# projekt.net
KiCad netlist of a schematic drawn in EAGLE
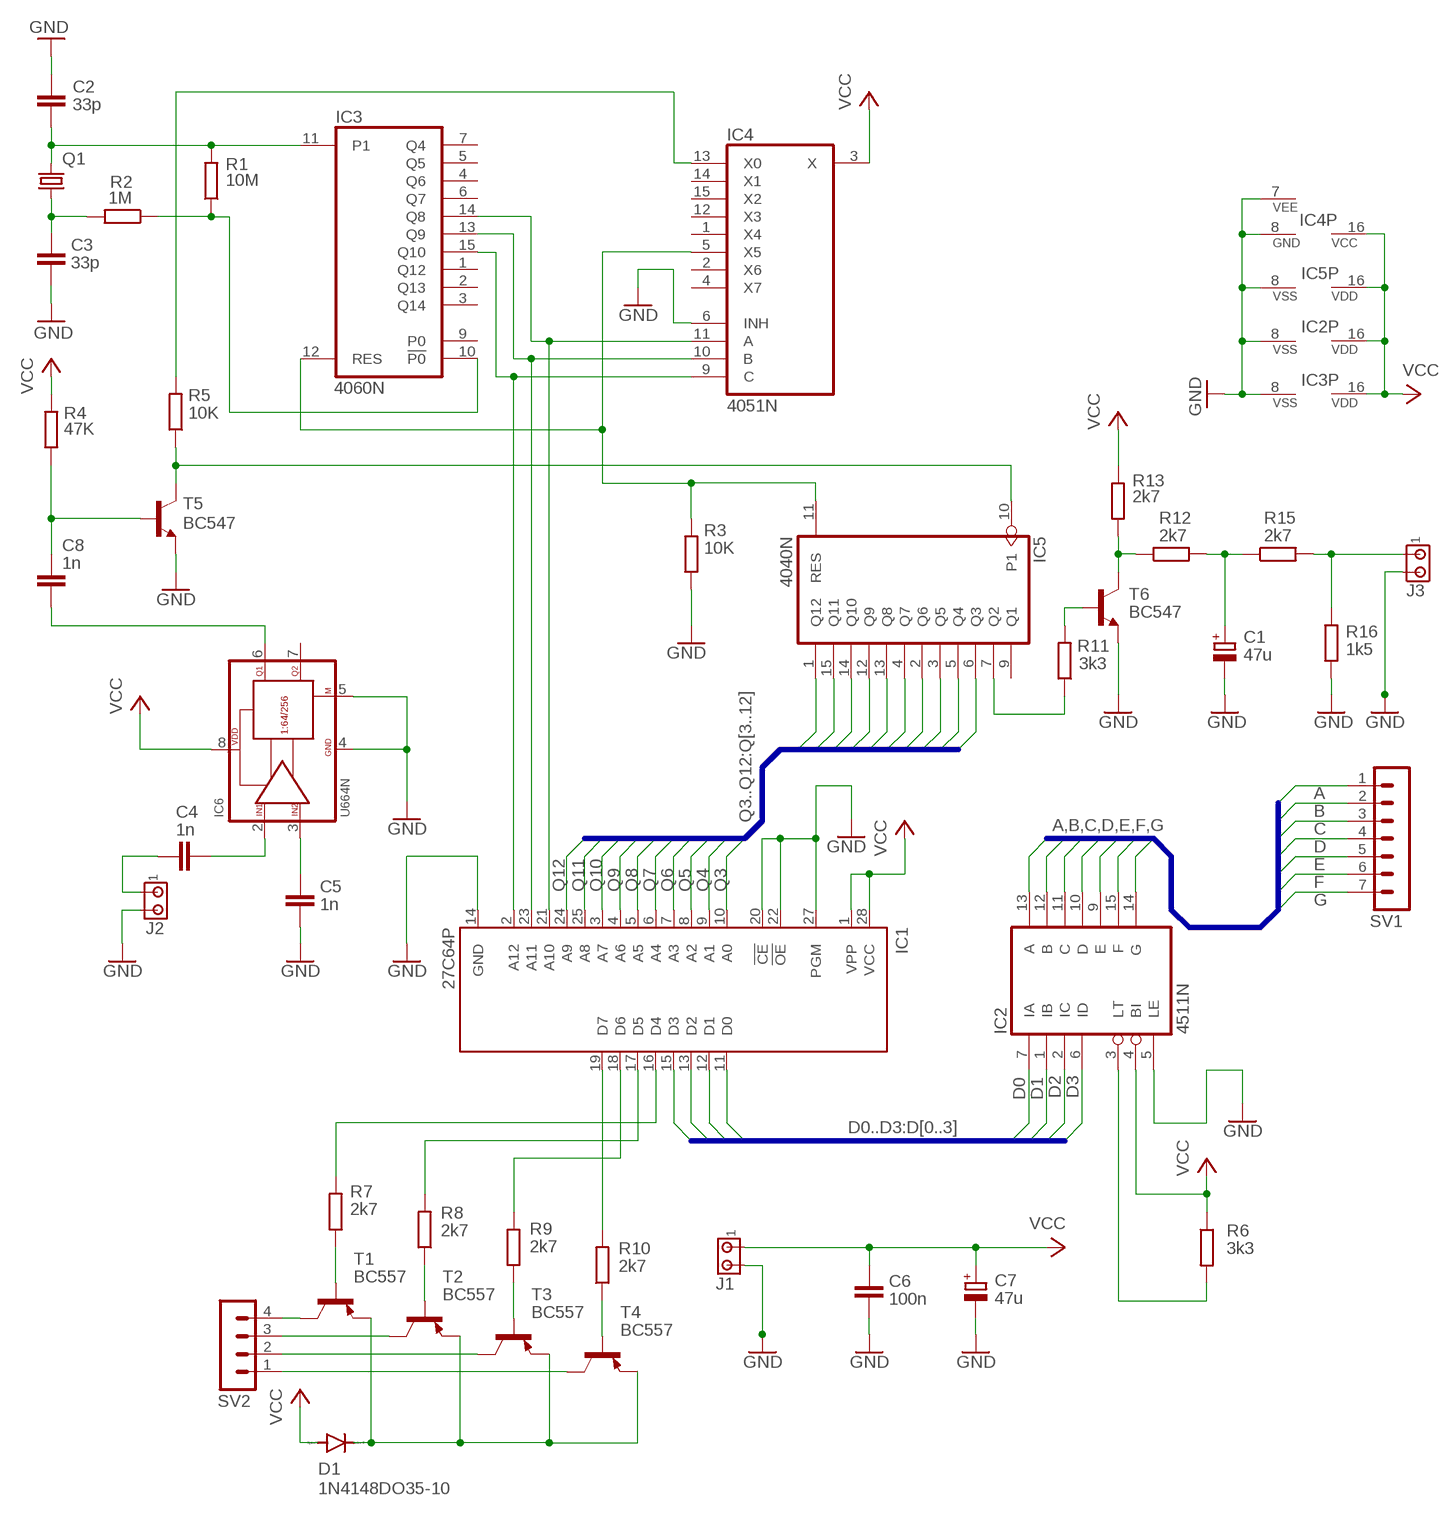
[diagram p0: schematic, sheet 1]

(export (version "E")
  (design (tool "Eeschema 10.0.6"))
  (components
    (comp (ref "C1")
      (value "47u")
      (footprint "eagle-import:E2,5-6")
      (libsource (lib "eagle-import") (part "CPOL-EUE2.5-6"))
    )
    (comp (ref "C2")
      (value "33p")
      (footprint "eagle-import:C025-025X050")
      (libsource (lib "eagle-import") (part "C-EU025-025X050"))
    )
    (comp (ref "C3")
      (value "33p")
      (footprint "eagle-import:C025-025X050")
      (libsource (lib "eagle-import") (part "C-EU025-025X050"))
    )
    (comp (ref "C4")
      (value "1n")
      (footprint "eagle-import:C025-025X050")
      (libsource (lib "eagle-import") (part "C-EU025-025X050"))
    )
    (comp (ref "C5")
      (value "1n")
      (footprint "eagle-import:C025-025X050")
      (libsource (lib "eagle-import") (part "C-EU025-025X050"))
    )
    (comp (ref "C6")
      (value "100n")
      (footprint "eagle-import:C025-025X050")
      (libsource (lib "eagle-import") (part "C-EU025-025X050"))
    )
    (comp (ref "C7")
      (value "47u")
      (footprint "eagle-import:E2,5-6")
      (libsource (lib "eagle-import") (part "CPOL-EUE2.5-6"))
    )
    (comp (ref "C8")
      (value "1n")
      (footprint "eagle-import:C025-025X050")
      (libsource (lib "eagle-import") (part "C-EU025-025X050"))
    )
    (comp (ref "D1")
      (value "1N4148DO35-10")
      (footprint "eagle-import:DO35-10")
      (libsource (lib "eagle-import") (part "1N4148DO35-10"))
    )
    (comp (ref "IC1")
      (value "27C64P")
      (footprint "eagle-import:DIL28-6")
      (fields (field (name "MF") "Arrow Electronics") (field (name "MPN") "M27C64A-10F1"))
      (libsource (lib "eagle-import") (part "2764PC"))
    )
    (comp (ref "IC2")
      (value "4511N")
      (footprint "eagle-import:DIL16")
      (libsource (lib "eagle-import") (part "4511N"))
    )
    (comp (ref "IC3")
      (value "4060N")
      (footprint "eagle-import:DIL16")
      (libsource (lib "eagle-import") (part "4060N"))
    )
    (comp (ref "IC4")
      (value "4051N")
      (footprint "eagle-import:DIL16")
      (libsource (lib "eagle-import") (part "4051N"))
    )
    (comp (ref "IC5")
      (value "4040N")
      (footprint "eagle-import:DIL16")
      (libsource (lib "eagle-import") (part "4040N"))
    )
    (comp (ref "IC6")
      (value "U664N")
      (footprint "eagle-import:DIL08")
      (libsource (lib "eagle-import") (part "U664N"))
    )
    (comp (ref "J1")
      (value "MTA02-100")
      (footprint "eagle-import:10X02MTA")
      (libsource (lib "eagle-import") (part "MTA02-100"))
    )
    (comp (ref "J2")
      (value "MTA02-100")
      (footprint "eagle-import:10X02MTA")
      (libsource (lib "eagle-import") (part "MTA02-100"))
    )
    (comp (ref "J3")
      (value "MTA02-100")
      (footprint "eagle-import:10X02MTA")
      (libsource (lib "eagle-import") (part "MTA02-100"))
    )
    (comp (ref "Q1")
      (value "CRYSTALHC49S")
      (footprint "eagle-import:HC49_S")
      (libsource (lib "eagle-import") (part "CRYSTALHC49S"))
    )
    (comp (ref "R1")
      (value "10M")
      (footprint "eagle-import:0207_10")
      (libsource (lib "eagle-import") (part "R-EU_0207/10"))
    )
    (comp (ref "R2")
      (value "1M")
      (footprint "eagle-import:0207_10")
      (libsource (lib "eagle-import") (part "R-EU_0207/10"))
    )
    (comp (ref "R3")
      (value "10K")
      (footprint "eagle-import:0207_10")
      (libsource (lib "eagle-import") (part "R-EU_0207/10"))
    )
    (comp (ref "R4")
      (value "47K")
      (footprint "eagle-import:0207_10")
      (libsource (lib "eagle-import") (part "R-EU_0207/10"))
    )
    (comp (ref "R5")
      (value "10K")
      (footprint "eagle-import:0207_10")
      (libsource (lib "eagle-import") (part "R-EU_0207/10"))
    )
    (comp (ref "R6")
      (value "3k3")
      (footprint "eagle-import:0207_10")
      (libsource (lib "eagle-import") (part "R-EU_0207/10"))
    )
    (comp (ref "R7")
      (value "2k7")
      (footprint "eagle-import:0207_10")
      (libsource (lib "eagle-import") (part "R-EU_0207/10"))
    )
    (comp (ref "R8")
      (value "2k7")
      (footprint "eagle-import:0207_10")
      (libsource (lib "eagle-import") (part "R-EU_0207/10"))
    )
    (comp (ref "R9")
      (value "2k7")
      (footprint "eagle-import:0207_10")
      (libsource (lib "eagle-import") (part "R-EU_0207/10"))
    )
    (comp (ref "R10")
      (value "2k7")
      (footprint "eagle-import:0207_10")
      (libsource (lib "eagle-import") (part "R-EU_0207/10"))
    )
    (comp (ref "R11")
      (value "3k3")
      (footprint "eagle-import:0207_10")
      (libsource (lib "eagle-import") (part "R-EU_0207/10"))
    )
    (comp (ref "R12")
      (value "2k7")
      (footprint "eagle-import:0207_10")
      (libsource (lib "eagle-import") (part "R-EU_0207/10"))
    )
    (comp (ref "R13")
      (value "2k7")
      (footprint "eagle-import:0207_10")
      (libsource (lib "eagle-import") (part "R-EU_0207/10"))
    )
    (comp (ref "R15")
      (value "2k7")
      (footprint "eagle-import:0207_10")
      (libsource (lib "eagle-import") (part "R-EU_0207/10"))
    )
    (comp (ref "R16")
      (value "1k5")
      (footprint "eagle-import:0207_10")
      (libsource (lib "eagle-import") (part "R-EU_0207/10"))
    )
    (comp (ref "SV1")
      (value "MA07-1")
      (footprint "eagle-import:MA07-1")
      (libsource (lib "eagle-import") (part "MA07-1"))
    )
    (comp (ref "SV2")
      (value "MA04-1")
      (footprint "eagle-import:MA04-1")
      (libsource (lib "eagle-import") (part "MA04-1"))
    )
    (comp (ref "T1")
      (value "BC557")
      (footprint "eagle-import:TO92")
      (libsource (lib "eagle-import") (part "BC557"))
    )
    (comp (ref "T2")
      (value "BC557")
      (footprint "eagle-import:TO92")
      (libsource (lib "eagle-import") (part "BC557"))
    )
    (comp (ref "T3")
      (value "BC557")
      (footprint "eagle-import:TO92")
      (libsource (lib "eagle-import") (part "BC557"))
    )
    (comp (ref "T4")
      (value "BC557")
      (footprint "eagle-import:TO92")
      (libsource (lib "eagle-import") (part "BC557"))
    )
    (comp (ref "T5")
      (value "BC547")
      (footprint "eagle-import:TO92")
      (libsource (lib "eagle-import") (part "BC547"))
    )
    (comp (ref "T6")
      (value "BC547")
      (footprint "eagle-import:TO92")
      (libsource (lib "eagle-import") (part "BC547"))
    )
  )
  (nets
    (net (code "15") (name "/A") (class "Default")
      (node (ref "IC2") (pin "13") (pinfunction "A_13") (pintype "output"))
      (node (ref "SV1") (pin "1") (pinfunction "1_1") (pintype "passive"))
    )
    (net (code "16") (name "/B") (class "Default")
      (node (ref "IC2") (pin "12") (pinfunction "B_12") (pintype "output"))
      (node (ref "SV1") (pin "2") (pinfunction "2_2") (pintype "passive"))
    )
    (net (code "17") (name "/C") (class "Default")
      (node (ref "IC2") (pin "11") (pinfunction "C_11") (pintype "output"))
      (node (ref "SV1") (pin "3") (pinfunction "3_3") (pintype "passive"))
    )
    (net (code "18") (name "/D") (class "Default")
      (node (ref "IC2") (pin "10") (pinfunction "D_10") (pintype "output"))
      (node (ref "SV1") (pin "4") (pinfunction "4_4") (pintype "passive"))
    )
    (net (code "19") (name "/D0") (class "Default")
      (node (ref "IC1") (pin "11") (pinfunction "D0_11") (pintype "tri_state"))
      (node (ref "IC2") (pin "7") (pinfunction "IA_7") (pintype "input"))
    )
    (net (code "21") (name "/D1") (class "Default")
      (node (ref "IC1") (pin "12") (pinfunction "D1_12") (pintype "tri_state"))
      (node (ref "IC2") (pin "1") (pinfunction "IB_1") (pintype "input"))
    )
    (net (code "22") (name "/D2") (class "Default")
      (node (ref "IC1") (pin "13") (pinfunction "D2_13") (pintype "tri_state"))
      (node (ref "IC2") (pin "2") (pinfunction "IC_2") (pintype "input"))
    )
    (net (code "23") (name "/D3") (class "Default")
      (node (ref "IC1") (pin "15") (pinfunction "D3_15") (pintype "tri_state"))
      (node (ref "IC2") (pin "6") (pinfunction "ID_6") (pintype "input"))
    )
    (net (code "24") (name "/E") (class "Default")
      (node (ref "IC2") (pin "9") (pinfunction "E_9") (pintype "output"))
      (node (ref "SV1") (pin "5") (pinfunction "5_5") (pintype "passive"))
    )
    (net (code "25") (name "/F") (class "Default")
      (node (ref "IC2") (pin "15") (pinfunction "F_15") (pintype "output"))
      (node (ref "SV1") (pin "6") (pinfunction "6_6") (pintype "passive"))
    )
    (net (code "26") (name "/G") (class "Default")
      (node (ref "IC2") (pin "14") (pinfunction "G_14") (pintype "output"))
      (node (ref "SV1") (pin "7") (pinfunction "7_7") (pintype "passive"))
    )
    (net (code "27") (name "/Q3") (class "Default")
      (node (ref "IC1") (pin "10") (pinfunction "A0_10") (pintype "input"))
      (node (ref "IC5") (pin "6") (pinfunction "Q3_6") (pintype "output"))
    )
    (net (code "29") (name "/Q4") (class "Default")
      (node (ref "IC1") (pin "9") (pinfunction "A1_9") (pintype "input"))
      (node (ref "IC5") (pin "5") (pinfunction "Q4_5") (pintype "output"))
    )
    (net (code "30") (name "/Q5") (class "Default")
      (node (ref "IC1") (pin "8") (pinfunction "A2_8") (pintype "input"))
      (node (ref "IC5") (pin "3") (pinfunction "Q5_3") (pintype "output"))
    )
    (net (code "31") (name "/Q6") (class "Default")
      (node (ref "IC1") (pin "7") (pinfunction "A3_7") (pintype "input"))
      (node (ref "IC5") (pin "2") (pinfunction "Q6_2") (pintype "output"))
    )
    (net (code "32") (name "/Q7") (class "Default")
      (node (ref "IC1") (pin "6") (pinfunction "A4_6") (pintype "input"))
      (node (ref "IC5") (pin "4") (pinfunction "Q7_4") (pintype "output"))
    )
    (net (code "33") (name "/Q8") (class "Default")
      (node (ref "IC1") (pin "5") (pinfunction "A5_5") (pintype "input"))
      (node (ref "IC5") (pin "13") (pinfunction "Q8_13") (pintype "output"))
    )
    (net (code "34") (name "/Q9") (class "Default")
      (node (ref "IC1") (pin "4") (pinfunction "A6_4") (pintype "input"))
      (node (ref "IC5") (pin "12") (pinfunction "Q9_12") (pintype "output"))
    )
    (net (code "35") (name "/Q10") (class "Default")
      (node (ref "IC1") (pin "3") (pinfunction "A7_3") (pintype "input"))
      (node (ref "IC5") (pin "14") (pinfunction "Q10_14") (pintype "output"))
    )
    (net (code "36") (name "/Q11") (class "Default")
      (node (ref "IC1") (pin "25") (pinfunction "A8_25") (pintype "input"))
      (node (ref "IC5") (pin "15") (pinfunction "Q11_15") (pintype "output"))
    )
    (net (code "37") (name "/Q12") (class "Default")
      (node (ref "IC1") (pin "24") (pinfunction "A9_24") (pintype "input"))
      (node (ref "IC5") (pin "1") (pinfunction "Q12_1") (pintype "output"))
    )
    (net (code "39") (name "GND") (class "Default")
      (node (ref "C1") (pin "-") (pinfunction "-_-") (pintype "passive"))
      (node (ref "C2") (pin "1") (pinfunction "1_1") (pintype "passive"))
      (node (ref "C3") (pin "2") (pinfunction "2_2") (pintype "passive"))
      (node (ref "C5") (pin "2") (pinfunction "2_2") (pintype "passive"))
      (node (ref "C6") (pin "2") (pinfunction "2_2") (pintype "passive"))
      (node (ref "C7") (pin "-") (pinfunction "-_-") (pintype "passive"))
      (node (ref "IC1") (pin "14") (pinfunction "GND_14") (pintype "power_in"))
      (node (ref "IC1") (pin "20") (pinfunction "~{CE}_20") (pintype "input"))
      (node (ref "IC1") (pin "22") (pinfunction "~{OE}_22") (pintype "input"))
      (node (ref "IC1") (pin "27") (pinfunction "PGM_27") (pintype "input"))
      (node (ref "IC2") (pin "5") (pinfunction "LE_5") (pintype "input"))
      (node (ref "IC2") (pin "8") (pinfunction "VSS_8") (pintype "power_in"))
      (node (ref "IC3") (pin "8") (pinfunction "VSS_8") (pintype "power_in"))
      (node (ref "IC4") (pin "6") (pinfunction "INH_6") (pintype "input"))
      (node (ref "IC4") (pin "7") (pinfunction "VEE_7") (pintype "power_in"))
      (node (ref "IC4") (pin "8") (pinfunction "GND_8") (pintype "power_in"))
      (node (ref "IC5") (pin "8") (pinfunction "VSS_8") (pintype "power_in"))
      (node (ref "IC6") (pin "4") (pinfunction "GND_4") (pintype "power_in"))
      (node (ref "IC6") (pin "5") (pinfunction "FAKT_5") (pintype "input"))
      (node (ref "J1") (pin "2") (pinfunction "2_2") (pintype "passive"))
      (node (ref "J2") (pin "2") (pinfunction "2_2") (pintype "passive"))
      (node (ref "J3") (pin "2") (pinfunction "2_2") (pintype "passive"))
      (node (ref "R16") (pin "1") (pinfunction "1_1") (pintype "passive"))
      (node (ref "R3") (pin "1") (pinfunction "1_1") (pintype "passive"))
      (node (ref "T5") (pin "1") (pinfunction "E_1") (pintype "passive"))
      (node (ref "T6") (pin "1") (pinfunction "E_1") (pintype "passive"))
    )
    (net (code "40") (name "Net-(C1-Pad+)") (class "Default")
      (node (ref "C1") (pin "+") (pinfunction "+_+") (pintype "passive"))
      (node (ref "R12") (pin "2") (pinfunction "2_2") (pintype "passive"))
      (node (ref "R15") (pin "1") (pinfunction "1_1") (pintype "passive"))
    )
    (net (code "41") (name "Net-(C3-Pad1)") (class "Default")
      (node (ref "C3") (pin "1") (pinfunction "1_1") (pintype "passive"))
      (node (ref "Q1") (pin "1") (pinfunction "1_1") (pintype "passive"))
      (node (ref "R2") (pin "2") (pinfunction "2_2") (pintype "passive"))
    )
    (net (code "42") (name "Net-(C4-Pad1)") (class "Default")
      (node (ref "C4") (pin "1") (pinfunction "1_1") (pintype "passive"))
      (node (ref "J2") (pin "1") (pinfunction "1_1") (pintype "passive"))
    )
    (net (code "43") (name "Net-(IC1-A10)") (class "Default")
      (node (ref "IC1") (pin "21") (pinfunction "A10_21") (pintype "input"))
      (node (ref "IC3") (pin "14") (pinfunction "Q8_14") (pintype "output"))
      (node (ref "IC4") (pin "11") (pinfunction "A_11") (pintype "input"))
    )
    (net (code "44") (name "Net-(IC1-A11)") (class "Default")
      (node (ref "IC1") (pin "23") (pinfunction "A11_23") (pintype "input"))
      (node (ref "IC3") (pin "13") (pinfunction "Q9_13") (pintype "output"))
      (node (ref "IC4") (pin "10") (pinfunction "B_10") (pintype "input"))
    )
    (net (code "45") (name "Net-(IC1-A12)") (class "Default")
      (node (ref "IC1") (pin "2") (pinfunction "A12_2") (pintype "input"))
      (node (ref "IC3") (pin "15") (pinfunction "Q10_15") (pintype "output"))
      (node (ref "IC4") (pin "9") (pinfunction "C_9") (pintype "input"))
    )
    (net (code "46") (name "Net-(IC1-D4)") (class "Default")
      (node (ref "IC1") (pin "16") (pinfunction "D4_16") (pintype "tri_state"))
      (node (ref "R7") (pin "2") (pinfunction "2_2") (pintype "passive"))
    )
    (net (code "47") (name "Net-(IC1-D5)") (class "Default")
      (node (ref "IC1") (pin "17") (pinfunction "D5_17") (pintype "tri_state"))
      (node (ref "R8") (pin "2") (pinfunction "2_2") (pintype "passive"))
    )
    (net (code "48") (name "Net-(IC1-D6)") (class "Default")
      (node (ref "IC1") (pin "18") (pinfunction "D6_18") (pintype "tri_state"))
      (node (ref "R9") (pin "2") (pinfunction "2_2") (pintype "passive"))
    )
    (net (code "49") (name "Net-(IC1-D7)") (class "Default")
      (node (ref "IC1") (pin "19") (pinfunction "D7_19") (pintype "tri_state"))
      (node (ref "R10") (pin "2") (pinfunction "2_2") (pintype "passive"))
    )
    (net (code "50") (name "Net-(IC2A-LT)") (class "Default")
      (node (ref "IC2") (pin "3") (pinfunction "LT_3") (pintype "input"))
      (node (ref "R6") (pin "2") (pinfunction "2_2") (pintype "passive"))
    )
    (net (code "51") (name "Net-(IC3A-P1)") (class "Default")
      (node (ref "C2") (pin "2") (pinfunction "2_2") (pintype "passive"))
      (node (ref "IC3") (pin "11") (pinfunction "P1_11") (pintype "input"))
      (node (ref "Q1") (pin "2") (pinfunction "2_2") (pintype "passive"))
      (node (ref "R1") (pin "2") (pinfunction "2_2") (pintype "passive"))
    )
    (net (code "52") (name "Net-(IC3A-RES)") (class "Default")
      (node (ref "IC3") (pin "12") (pinfunction "RES_12") (pintype "input"))
      (node (ref "IC4") (pin "5") (pinfunction "X5_5") (pintype "bidirectional"))
      (node (ref "IC5") (pin "11") (pinfunction "RES_11") (pintype "input"))
      (node (ref "R3") (pin "2") (pinfunction "2_2") (pintype "passive"))
    )
    (net (code "53") (name "Net-(IC3A-~{P0})") (class "Default")
      (node (ref "IC3") (pin "10") (pinfunction "~{P0}_10") (pintype "output"))
      (node (ref "R1") (pin "1") (pinfunction "1_1") (pintype "passive"))
      (node (ref "R2") (pin "1") (pinfunction "1_1") (pintype "passive"))
    )
    (net (code "54") (name "Net-(IC4A-X0)") (class "Default")
      (node (ref "IC4") (pin "13") (pinfunction "X0_13") (pintype "bidirectional"))
      (node (ref "R5") (pin "2") (pinfunction "2_2") (pintype "passive"))
    )
    (net (code "55") (name "Net-(IC5A-P1)") (class "Default")
      (node (ref "IC5") (pin "10") (pinfunction "P1_10") (pintype "input"))
      (node (ref "R5") (pin "1") (pinfunction "1_1") (pintype "passive"))
      (node (ref "T5") (pin "3") (pinfunction "C_3") (pintype "passive"))
    )
    (net (code "56") (name "Net-(IC5A-Q2)") (class "Default")
      (node (ref "IC5") (pin "7") (pinfunction "Q2_7") (pintype "output"))
      (node (ref "R11") (pin "1") (pinfunction "1_1") (pintype "passive"))
    )
    (net (code "57") (name "Net-(IC6-I1)") (class "Default")
      (node (ref "C4") (pin "2") (pinfunction "2_2") (pintype "passive"))
      (node (ref "IC6") (pin "2") (pinfunction "I1_2") (pintype "input"))
    )
    (net (code "58") (name "Net-(IC6-I2)") (class "Default")
      (node (ref "C5") (pin "1") (pinfunction "1_1") (pintype "passive"))
      (node (ref "IC6") (pin "3") (pinfunction "I2_3") (pintype "input"))
    )
    (net (code "59") (name "Net-(IC6-O1)") (class "Default")
      (node (ref "C8") (pin "2") (pinfunction "2_2") (pintype "passive"))
      (node (ref "IC6") (pin "6") (pinfunction "O1_6") (pintype "output"))
    )
    (net (code "60") (name "Net-(J3-Pad1)") (class "Default")
      (node (ref "J3") (pin "1") (pinfunction "1_1") (pintype "passive"))
      (node (ref "R15") (pin "2") (pinfunction "2_2") (pintype "passive"))
      (node (ref "R16") (pin "2") (pinfunction "2_2") (pintype "passive"))
    )
    (net (code "61") (name "Net-(T1-B)") (class "Default")
      (node (ref "R7") (pin "1") (pinfunction "1_1") (pintype "passive"))
      (node (ref "T1") (pin "2") (pinfunction "B_2") (pintype "passive"))
    )
    (net (code "62") (name "Net-(T1-C)") (class "Default")
      (node (ref "SV2") (pin "4") (pinfunction "4_4") (pintype "passive"))
      (node (ref "T1") (pin "3") (pinfunction "C_3") (pintype "passive"))
    )
    (net (code "63") (name "Net-(T1-E)") (class "Default")
      (node (ref "D1") (pin "C") (pinfunction "C_C") (pintype "passive"))
      (node (ref "T1") (pin "1") (pinfunction "E_1") (pintype "passive"))
      (node (ref "T2") (pin "1") (pinfunction "E_1") (pintype "passive"))
      (node (ref "T3") (pin "1") (pinfunction "E_1") (pintype "passive"))
      (node (ref "T4") (pin "1") (pinfunction "E_1") (pintype "passive"))
    )
    (net (code "64") (name "Net-(T2-B)") (class "Default")
      (node (ref "R8") (pin "1") (pinfunction "1_1") (pintype "passive"))
      (node (ref "T2") (pin "2") (pinfunction "B_2") (pintype "passive"))
    )
    (net (code "65") (name "Net-(T2-C)") (class "Default")
      (node (ref "SV2") (pin "3") (pinfunction "3_3") (pintype "passive"))
      (node (ref "T2") (pin "3") (pinfunction "C_3") (pintype "passive"))
    )
    (net (code "66") (name "Net-(T3-B)") (class "Default")
      (node (ref "R9") (pin "1") (pinfunction "1_1") (pintype "passive"))
      (node (ref "T3") (pin "2") (pinfunction "B_2") (pintype "passive"))
    )
    (net (code "67") (name "Net-(T3-C)") (class "Default")
      (node (ref "SV2") (pin "2") (pinfunction "2_2") (pintype "passive"))
      (node (ref "T3") (pin "3") (pinfunction "C_3") (pintype "passive"))
    )
    (net (code "68") (name "Net-(T4-B)") (class "Default")
      (node (ref "R10") (pin "1") (pinfunction "1_1") (pintype "passive"))
      (node (ref "T4") (pin "2") (pinfunction "B_2") (pintype "passive"))
    )
    (net (code "69") (name "Net-(T4-C)") (class "Default")
      (node (ref "SV2") (pin "1") (pinfunction "1_1") (pintype "passive"))
      (node (ref "T4") (pin "3") (pinfunction "C_3") (pintype "passive"))
    )
    (net (code "70") (name "Net-(T5-B)") (class "Default")
      (node (ref "C8") (pin "1") (pinfunction "1_1") (pintype "passive"))
      (node (ref "R4") (pin "1") (pinfunction "1_1") (pintype "passive"))
      (node (ref "T5") (pin "2") (pinfunction "B_2") (pintype "passive"))
    )
    (net (code "71") (name "Net-(T6-B)") (class "Default")
      (node (ref "R11") (pin "2") (pinfunction "2_2") (pintype "passive"))
      (node (ref "T6") (pin "2") (pinfunction "B_2") (pintype "passive"))
    )
    (net (code "72") (name "Net-(T6-C)") (class "Default")
      (node (ref "R12") (pin "1") (pinfunction "1_1") (pintype "passive"))
      (node (ref "R13") (pin "2") (pinfunction "2_2") (pintype "passive"))
      (node (ref "T6") (pin "3") (pinfunction "C_3") (pintype "passive"))
    )
    (net (code "73") (name "VCC") (class "Default")
      (node (ref "C6") (pin "1") (pinfunction "1_1") (pintype "passive"))
      (node (ref "C7") (pin "+") (pinfunction "+_+") (pintype "passive"))
      (node (ref "D1") (pin "A") (pinfunction "A_A") (pintype "passive"))
      (node (ref "IC1") (pin "1") (pinfunction "VPP_1") (pintype "input"))
      (node (ref "IC1") (pin "28") (pinfunction "VCC_28") (pintype "power_in"))
      (node (ref "IC2") (pin "16") (pinfunction "VDD_16") (pintype "power_in"))
      (node (ref "IC2") (pin "4") (pinfunction "BI_4") (pintype "input"))
      (node (ref "IC3") (pin "16") (pinfunction "VDD_16") (pintype "power_in"))
      (node (ref "IC4") (pin "16") (pinfunction "VCC_16") (pintype "power_in"))
      (node (ref "IC4") (pin "3") (pinfunction "X_3") (pintype "bidirectional"))
      (node (ref "IC5") (pin "16") (pinfunction "VDD_16") (pintype "power_in"))
      (node (ref "IC6") (pin "8") (pinfunction "VPP_8") (pintype "power_in"))
      (node (ref "J1") (pin "1") (pinfunction "1_1") (pintype "passive"))
      (node (ref "R13") (pin "1") (pinfunction "1_1") (pintype "passive"))
      (node (ref "R4") (pin "2") (pinfunction "2_2") (pintype "passive"))
      (node (ref "R6") (pin "1") (pinfunction "1_1") (pintype "passive"))
    )
    (net (code "74") (name "unconnected-(IC1-NC-Pad26)") (class "Default")
      (node (ref "IC1") (pin "26") (pinfunction "NC_26") (pintype "no_connect"))
    )
    (net (code "75") (name "unconnected-(IC3A-P0-Pad9)") (class "Default")
      (node (ref "IC3") (pin "9") (pinfunction "P0_9") (pintype "output"))
    )
    (net (code "76") (name "unconnected-(IC3A-Q4-Pad7)") (class "Default")
      (node (ref "IC3") (pin "7") (pinfunction "Q4_7") (pintype "output"))
    )
    (net (code "77") (name "unconnected-(IC3A-Q5-Pad5)") (class "Default")
      (node (ref "IC3") (pin "5") (pinfunction "Q5_5") (pintype "output"))
    )
    (net (code "78") (name "unconnected-(IC3A-Q6-Pad4)") (class "Default")
      (node (ref "IC3") (pin "4") (pinfunction "Q6_4") (pintype "output"))
    )
    (net (code "79") (name "unconnected-(IC3A-Q7-Pad6)") (class "Default")
      (node (ref "IC3") (pin "6") (pinfunction "Q7_6") (pintype "output"))
    )
    (net (code "80") (name "unconnected-(IC3A-Q12-Pad1)") (class "Default")
      (node (ref "IC3") (pin "1") (pinfunction "Q12_1") (pintype "output"))
    )
    (net (code "81") (name "unconnected-(IC3A-Q13-Pad2)") (class "Default")
      (node (ref "IC3") (pin "2") (pinfunction "Q13_2") (pintype "output"))
    )
    (net (code "82") (name "unconnected-(IC3A-Q14-Pad3)") (class "Default")
      (node (ref "IC3") (pin "3") (pinfunction "Q14_3") (pintype "output"))
    )
    (net (code "83") (name "unconnected-(IC4A-X1-Pad14)") (class "Default")
      (node (ref "IC4") (pin "14") (pinfunction "X1_14") (pintype "bidirectional"))
    )
    (net (code "84") (name "unconnected-(IC4A-X2-Pad15)") (class "Default")
      (node (ref "IC4") (pin "15") (pinfunction "X2_15") (pintype "bidirectional"))
    )
    (net (code "85") (name "unconnected-(IC4A-X3-Pad12)") (class "Default")
      (node (ref "IC4") (pin "12") (pinfunction "X3_12") (pintype "bidirectional"))
    )
    (net (code "86") (name "unconnected-(IC4A-X4-Pad1)") (class "Default")
      (node (ref "IC4") (pin "1") (pinfunction "X4_1") (pintype "bidirectional"))
    )
    (net (code "87") (name "unconnected-(IC4A-X6-Pad2)") (class "Default")
      (node (ref "IC4") (pin "2") (pinfunction "X6_2") (pintype "bidirectional"))
    )
    (net (code "88") (name "unconnected-(IC4A-X7-Pad4)") (class "Default")
      (node (ref "IC4") (pin "4") (pinfunction "X7_4") (pintype "bidirectional"))
    )
    (net (code "89") (name "unconnected-(IC5A-Q1-Pad9)") (class "Default")
      (node (ref "IC5") (pin "9") (pinfunction "Q1_9") (pintype "output"))
    )
    (net (code "90") (name "unconnected-(IC6-O2-Pad7)") (class "Default")
      (node (ref "IC6") (pin "7") (pinfunction "O2_7") (pintype "output"))
    )
  )
)
